# HX4002_CE021_MAX40200.net
KiCad netlist of a schematic drawn in EAGLE
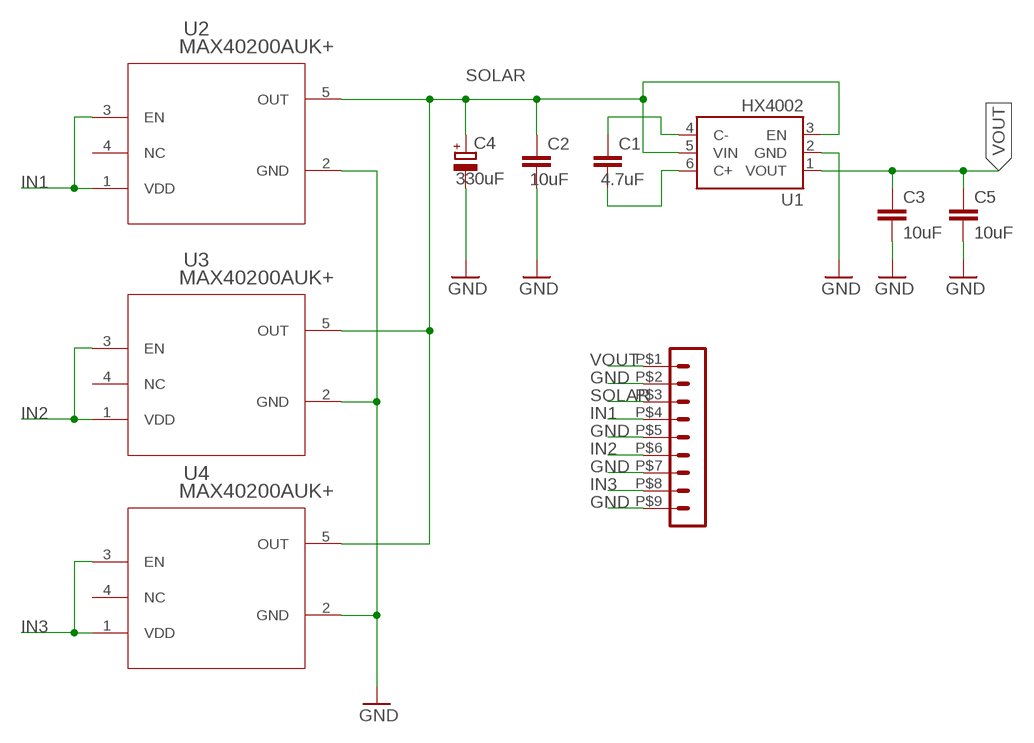
[diagram p0: schematic, sheet 1]

(export (version "E")
  (design (tool "Eeschema 10.0.6"))
  (components
    (comp (ref "C1")
      (value "4.7uF")
      (footprint "eagle-import:0805")
      (libsource (lib "eagle-import") (part "CAP-0805"))
    )
    (comp (ref "C2")
      (value "10uF")
      (footprint "eagle-import:0805")
      (libsource (lib "eagle-import") (part "CAP-0805"))
    )
    (comp (ref "C3")
      (value "10uF")
      (footprint "eagle-import:0805")
      (libsource (lib "eagle-import") (part "CAP-0805"))
    )
    (comp (ref "C4")
      (value "330uF")
      (footprint "eagle-import:SMC_C")
      (libsource (lib "eagle-import") (part "CPOL-EUSMCC"))
    )
    (comp (ref "C5")
      (value "10uF")
      (footprint "eagle-import:0805")
      (libsource (lib "eagle-import") (part "CAP-0805"))
    )
    (comp (ref "U1")
      (value "HX4002")
      (footprint "eagle-import:SOT23-6")
      (libsource (lib "eagle-import") (part "CE021SOT-23"))
    )
    (comp (ref "U2")
      (value "MAX40200AUK+")
      (footprint "eagle-import:21-0057F_MXM")
      (fields (field (name "COPYRIGHT") "Copyright (C) 2018 Accelerated Designs. All rights reserved"))
      (libsource (lib "eagle-import") (part "MAX40200AUK+"))
    )
    (comp (ref "U3")
      (value "MAX40200AUK+")
      (footprint "eagle-import:21-0057F_MXM")
      (fields (field (name "COPYRIGHT") "Copyright (C) 2018 Accelerated Designs. All rights reserved"))
      (libsource (lib "eagle-import") (part "MAX40200AUK+"))
    )
    (comp (ref "U4")
      (value "MAX40200AUK+")
      (footprint "eagle-import:21-0057F_MXM")
      (fields (field (name "COPYRIGHT") "Copyright (C) 2018 Accelerated Designs. All rights reserved"))
      (libsource (lib "eagle-import") (part "MAX40200AUK+"))
    )
    (comp (ref "X2")
      (value "M_1R09_50MIL-V")
      (footprint "eagle-import:M_1R09_50MIL-V")
      (libsource (lib "eagle-import") (part "M_1R09_50MIL-V"))
    )
  )
  (nets
    (net (code "1") (name "/IN1") (class "Default")
      (node (ref "U2") (pin "1") (pinfunction "VDD_1") (pintype "power_in"))
      (node (ref "U2") (pin "3") (pinfunction "EN_3") (pintype "passive"))
      (node (ref "X2") (pin "P$4") (pinfunction "4_P$4") (pintype "bidirectional"))
    )
    (net (code "2") (name "/IN2") (class "Default")
      (node (ref "U3") (pin "1") (pinfunction "VDD_1") (pintype "power_in"))
      (node (ref "U3") (pin "3") (pinfunction "EN_3") (pintype "passive"))
      (node (ref "X2") (pin "P$6") (pinfunction "6_P$6") (pintype "bidirectional"))
    )
    (net (code "3") (name "/IN3") (class "Default")
      (node (ref "U4") (pin "1") (pinfunction "VDD_1") (pintype "power_in"))
      (node (ref "U4") (pin "3") (pinfunction "EN_3") (pintype "passive"))
      (node (ref "X2") (pin "P$8") (pinfunction "8_P$8") (pintype "bidirectional"))
    )
    (net (code "4") (name "/SOLAR") (class "Default")
      (node (ref "C2") (pin "1") (pinfunction "1_1") (pintype "passive"))
      (node (ref "C4") (pin "+") (pinfunction "+_+") (pintype "passive"))
      (node (ref "U1") (pin "3") (pinfunction "EN_3") (pintype "bidirectional"))
      (node (ref "U1") (pin "5") (pinfunction "VIN_5") (pintype "bidirectional"))
      (node (ref "U2") (pin "5") (pinfunction "OUT_5") (pintype "output"))
      (node (ref "U3") (pin "5") (pinfunction "OUT_5") (pintype "output"))
      (node (ref "U4") (pin "5") (pinfunction "OUT_5") (pintype "output"))
      (node (ref "X2") (pin "P$3") (pinfunction "3_P$3") (pintype "bidirectional"))
    )
    (net (code "5") (name "GND") (class "Default")
      (node (ref "C2") (pin "2") (pinfunction "2_2") (pintype "passive"))
      (node (ref "C3") (pin "2") (pinfunction "2_2") (pintype "passive"))
      (node (ref "C4") (pin "-") (pinfunction "-_-") (pintype "passive"))
      (node (ref "C5") (pin "2") (pinfunction "2_2") (pintype "passive"))
      (node (ref "U1") (pin "2") (pinfunction "GND_2") (pintype "bidirectional"))
      (node (ref "U2") (pin "2") (pinfunction "GND_2") (pintype "passive"))
      (node (ref "U3") (pin "2") (pinfunction "GND_2") (pintype "passive"))
      (node (ref "U4") (pin "2") (pinfunction "GND_2") (pintype "passive"))
      (node (ref "X2") (pin "P$2") (pinfunction "2_P$2") (pintype "bidirectional"))
      (node (ref "X2") (pin "P$5") (pinfunction "5_P$5") (pintype "bidirectional"))
      (node (ref "X2") (pin "P$7") (pinfunction "7_P$7") (pintype "bidirectional"))
      (node (ref "X2") (pin "P$9") (pinfunction "9_P$9") (pintype "bidirectional"))
    )
    (net (code "6") (name "Net-(U1-C+)") (class "Default")
      (node (ref "C1") (pin "2") (pinfunction "2_2") (pintype "passive"))
      (node (ref "U1") (pin "6") (pinfunction "C+_6") (pintype "bidirectional"))
    )
    (net (code "7") (name "Net-(U1-C-)") (class "Default")
      (node (ref "C1") (pin "1") (pinfunction "1_1") (pintype "passive"))
      (node (ref "U1") (pin "4") (pinfunction "C-_4") (pintype "bidirectional"))
    )
    (net (code "8") (name "VOUT") (class "Default")
      (node (ref "C3") (pin "1") (pinfunction "1_1") (pintype "passive"))
      (node (ref "C5") (pin "1") (pinfunction "1_1") (pintype "passive"))
      (node (ref "U1") (pin "1") (pinfunction "VOUT_1") (pintype "bidirectional"))
      (node (ref "X2") (pin "P$1") (pinfunction "1_P$1") (pintype "bidirectional"))
    )
    (net (code "9") (name "unconnected-(U2-NC-Pad4)") (class "Default")
      (node (ref "U2") (pin "4") (pinfunction "NC_4") (pintype "no_connect"))
    )
    (net (code "10") (name "unconnected-(U3-NC-Pad4)") (class "Default")
      (node (ref "U3") (pin "4") (pinfunction "NC_4") (pintype "no_connect"))
    )
    (net (code "11") (name "unconnected-(U4-NC-Pad4)") (class "Default")
      (node (ref "U4") (pin "4") (pinfunction "NC_4") (pintype "no_connect"))
    )
  )
)
